# LEDmatrix2.net
KiCad netlist of a schematic drawn in Altium Designer
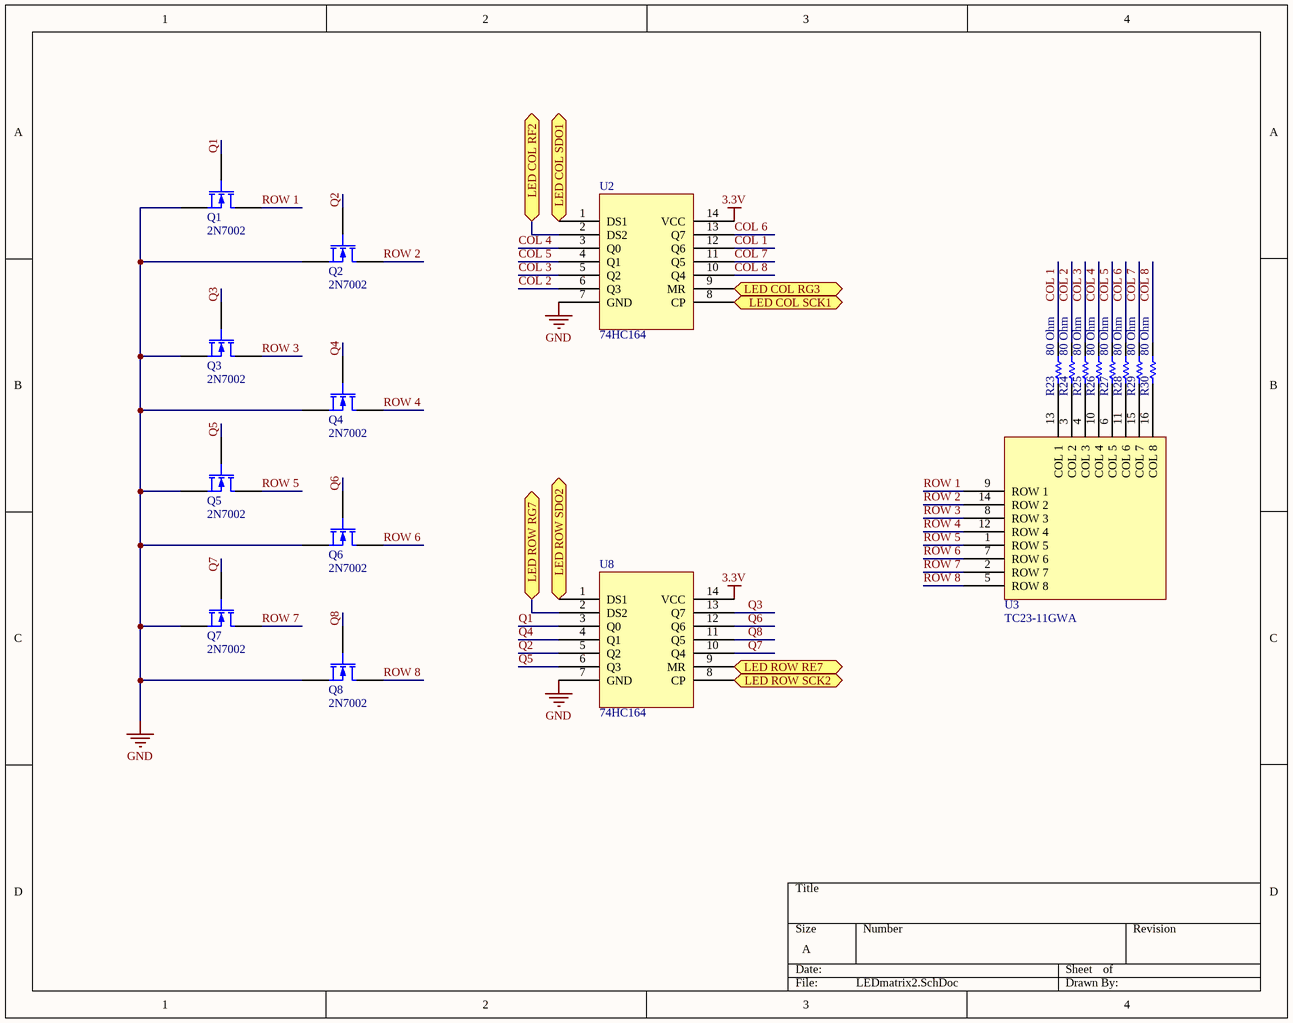
[diagram p0: LEDmatrix2.SchDoc]

(export (version "E")
  (design (tool "Eeschema 10.0.6"))
  (components
    (comp (ref "Q1")
      (value "2N7002")
      (footprint "Mosfet")
      (description "N-Channel MOSFET")
      (fields (field (name "PUBLISHER") "Altium Limited"))
      (libsource (lib "Miscellaneous Devices") (part "MOSFET-N"))
    )
    (comp (ref "Q2")
      (value "2N7002")
      (footprint "Mosfet")
      (description "N-Channel MOSFET")
      (fields (field (name "PUBLISHER") "Altium Limited"))
      (libsource (lib "Miscellaneous Devices") (part "MOSFET-N"))
    )
    (comp (ref "Q3")
      (value "2N7002")
      (footprint "Mosfet")
      (description "N-Channel MOSFET")
      (fields (field (name "PUBLISHER") "Altium Limited"))
      (libsource (lib "Miscellaneous Devices") (part "MOSFET-N"))
    )
    (comp (ref "Q4")
      (value "2N7002")
      (footprint "Mosfet")
      (description "N-Channel MOSFET")
      (fields (field (name "PUBLISHER") "Altium Limited"))
      (libsource (lib "Miscellaneous Devices") (part "MOSFET-N"))
    )
    (comp (ref "Q5")
      (value "2N7002")
      (footprint "Mosfet")
      (description "N-Channel MOSFET")
      (fields (field (name "PUBLISHER") "Altium Limited"))
      (libsource (lib "Miscellaneous Devices") (part "MOSFET-N"))
    )
    (comp (ref "Q6")
      (value "2N7002")
      (footprint "Mosfet")
      (description "N-Channel MOSFET")
      (fields (field (name "PUBLISHER") "Altium Limited"))
      (libsource (lib "Miscellaneous Devices") (part "MOSFET-N"))
    )
    (comp (ref "Q7")
      (value "2N7002")
      (footprint "Mosfet")
      (description "N-Channel MOSFET")
      (fields (field (name "PUBLISHER") "Altium Limited"))
      (libsource (lib "Miscellaneous Devices") (part "MOSFET-N"))
    )
    (comp (ref "Q8")
      (value "2N7002")
      (footprint "Mosfet")
      (description "N-Channel MOSFET")
      (fields (field (name "PUBLISHER") "Altium Limited"))
      (libsource (lib "Miscellaneous Devices") (part "MOSFET-N"))
    )
    (comp (ref "R23")
      (value "80 Ohm")
      (footprint "Resistor0603")
      (description "Resistor")
      (fields (field (name "PUBLISHER") "Altium Limited"))
      (libsource (lib "Miscellaneous Devices") (part "Res1"))
    )
    (comp (ref "R24")
      (value "80 Ohm")
      (footprint "Resistor0603")
      (description "Resistor")
      (fields (field (name "PUBLISHER") "Altium Limited"))
      (libsource (lib "Miscellaneous Devices") (part "Res1"))
    )
    (comp (ref "R25")
      (value "80 Ohm")
      (footprint "Resistor0603")
      (description "Resistor")
      (fields (field (name "PUBLISHER") "Altium Limited"))
      (libsource (lib "Miscellaneous Devices") (part "Res1"))
    )
    (comp (ref "R26")
      (value "80 Ohm")
      (footprint "Resistor0603")
      (description "Resistor")
      (fields (field (name "PUBLISHER") "Altium Limited"))
      (libsource (lib "Miscellaneous Devices") (part "Res1"))
    )
    (comp (ref "R27")
      (value "80 Ohm")
      (footprint "Resistor0603")
      (description "Resistor")
      (fields (field (name "PUBLISHER") "Altium Limited"))
      (libsource (lib "Miscellaneous Devices") (part "Res1"))
    )
    (comp (ref "R28")
      (value "80 Ohm")
      (footprint "Resistor0603")
      (description "Resistor")
      (fields (field (name "PUBLISHER") "Altium Limited"))
      (libsource (lib "Miscellaneous Devices") (part "Res1"))
    )
    (comp (ref "R29")
      (value "80 Ohm")
      (footprint "Resistor0603")
      (description "Resistor")
      (fields (field (name "PUBLISHER") "Altium Limited"))
      (libsource (lib "Miscellaneous Devices") (part "Res1"))
    )
    (comp (ref "R30")
      (value "80 Ohm")
      (footprint "Resistor0603")
      (description "Resistor")
      (fields (field (name "PUBLISHER") "Altium Limited"))
      (libsource (lib "Miscellaneous Devices") (part "Res1"))
    )
    (comp (ref "U2")
      (value "74HC164")
      (footprint "SHIFT REGISTER")
      (libsource (lib "PROBOT_Schema_Library") (part "Shift Register"))
    )
    (comp (ref "U3")
      (value "TC23-11GWA")
      (footprint "LEDPANEL")
      (libsource (lib "PROBOT_Schema_Library") (part "LED Dot Matrix"))
    )
    (comp (ref "U8")
      (value "74HC164")
      (footprint "SHIFT REGISTER")
      (libsource (lib "PROBOT_Schema_Library") (part "Shift Register"))
    )
  )
  (nets
    (net (code "1") (name "/COL 1") (class "Default")
      (node (ref "R23") (pin "2") (pinfunction "2_2") (pintype "passive"))
      (node (ref "U2") (pin "12") (pinfunction "Q6_12") (pintype "passive"))
    )
    (net (code "2") (name "/COL 2") (class "Default")
      (node (ref "R24") (pin "2") (pinfunction "2_2") (pintype "passive"))
      (node (ref "U2") (pin "6") (pinfunction "Q3_6") (pintype "passive"))
    )
    (net (code "3") (name "/COL 3") (class "Default")
      (node (ref "R25") (pin "2") (pinfunction "2_2") (pintype "passive"))
      (node (ref "U2") (pin "5") (pinfunction "Q2_5") (pintype "passive"))
    )
    (net (code "4") (name "/COL 4") (class "Default")
      (node (ref "R26") (pin "2") (pinfunction "2_2") (pintype "passive"))
      (node (ref "U2") (pin "3") (pinfunction "Q0_3") (pintype "passive"))
    )
    (net (code "5") (name "/COL 5") (class "Default")
      (node (ref "R27") (pin "2") (pinfunction "2_2") (pintype "passive"))
      (node (ref "U2") (pin "4") (pinfunction "Q1_4") (pintype "passive"))
    )
    (net (code "6") (name "/COL 6") (class "Default")
      (node (ref "R28") (pin "2") (pinfunction "2_2") (pintype "passive"))
      (node (ref "U2") (pin "13") (pinfunction "Q7_13") (pintype "passive"))
    )
    (net (code "7") (name "/COL 7") (class "Default")
      (node (ref "R29") (pin "2") (pinfunction "2_2") (pintype "passive"))
      (node (ref "U2") (pin "11") (pinfunction "Q5_11") (pintype "passive"))
    )
    (net (code "8") (name "/COL 8") (class "Default")
      (node (ref "R30") (pin "2") (pinfunction "2_2") (pintype "passive"))
      (node (ref "U2") (pin "10") (pinfunction "Q4_10") (pintype "passive"))
    )
    (net (code "9") (name "/LED COL RF2") (class "Default")
      (node (ref "U2") (pin "2") (pinfunction "DS2_2") (pintype "passive"))
    )
    (net (code "10") (name "/LED COL RG3") (class "Default")
      (node (ref "U2") (pin "9") (pinfunction "MR_9") (pintype "passive"))
    )
    (net (code "11") (name "/LED COL SCK1") (class "Default")
      (node (ref "U2") (pin "8") (pinfunction "CP_8") (pintype "passive"))
    )
    (net (code "12") (name "/LED COL SDO1") (class "Default")
      (node (ref "U2") (pin "1") (pinfunction "DS1_1") (pintype "passive"))
    )
    (net (code "13") (name "/LED ROW RE7") (class "Default")
      (node (ref "U8") (pin "9") (pinfunction "MR_9") (pintype "passive"))
    )
    (net (code "14") (name "/LED ROW RG7") (class "Default")
      (node (ref "U8") (pin "2") (pinfunction "DS2_2") (pintype "passive"))
    )
    (net (code "15") (name "/LED ROW SCK2") (class "Default")
      (node (ref "U8") (pin "8") (pinfunction "CP_8") (pintype "passive"))
    )
    (net (code "16") (name "/LED ROW SDO2") (class "Default")
      (node (ref "U8") (pin "1") (pinfunction "DS1_1") (pintype "passive"))
    )
    (net (code "17") (name "/Q1") (class "Default")
      (node (ref "Q1") (pin "2") (pinfunction "G_2") (pintype "passive"))
      (node (ref "U8") (pin "3") (pinfunction "Q0_3") (pintype "passive"))
    )
    (net (code "18") (name "/Q2") (class "Default")
      (node (ref "Q2") (pin "2") (pinfunction "G_2") (pintype "passive"))
      (node (ref "U8") (pin "5") (pinfunction "Q2_5") (pintype "passive"))
    )
    (net (code "19") (name "/Q3") (class "Default")
      (node (ref "Q3") (pin "2") (pinfunction "G_2") (pintype "passive"))
      (node (ref "U8") (pin "13") (pinfunction "Q7_13") (pintype "passive"))
    )
    (net (code "20") (name "/Q4") (class "Default")
      (node (ref "Q4") (pin "2") (pinfunction "G_2") (pintype "passive"))
      (node (ref "U8") (pin "4") (pinfunction "Q1_4") (pintype "passive"))
    )
    (net (code "21") (name "/Q5") (class "Default")
      (node (ref "Q5") (pin "2") (pinfunction "G_2") (pintype "passive"))
      (node (ref "U8") (pin "6") (pinfunction "Q3_6") (pintype "passive"))
    )
    (net (code "22") (name "/Q6") (class "Default")
      (node (ref "Q6") (pin "2") (pinfunction "G_2") (pintype "passive"))
      (node (ref "U8") (pin "12") (pinfunction "Q6_12") (pintype "passive"))
    )
    (net (code "23") (name "/Q7") (class "Default")
      (node (ref "Q7") (pin "2") (pinfunction "G_2") (pintype "passive"))
      (node (ref "U8") (pin "10") (pinfunction "Q4_10") (pintype "passive"))
    )
    (net (code "24") (name "/Q8") (class "Default")
      (node (ref "Q8") (pin "2") (pinfunction "G_2") (pintype "passive"))
      (node (ref "U8") (pin "11") (pinfunction "Q5_11") (pintype "passive"))
    )
    (net (code "25") (name "/ROW 1") (class "Default")
      (node (ref "Q1") (pin "1") (pinfunction "D_1") (pintype "passive"))
      (node (ref "U3") (pin "9") (pinfunction "ROW_1_9") (pintype "passive"))
    )
    (net (code "26") (name "/ROW 2") (class "Default")
      (node (ref "Q2") (pin "1") (pinfunction "D_1") (pintype "passive"))
      (node (ref "U3") (pin "14") (pinfunction "ROW_2_14") (pintype "passive"))
    )
    (net (code "27") (name "/ROW 3") (class "Default")
      (node (ref "Q3") (pin "1") (pinfunction "D_1") (pintype "passive"))
      (node (ref "U3") (pin "8") (pinfunction "ROW_3_8") (pintype "passive"))
    )
    (net (code "28") (name "/ROW 4") (class "Default")
      (node (ref "Q4") (pin "1") (pinfunction "D_1") (pintype "passive"))
      (node (ref "U3") (pin "12") (pinfunction "ROW_4_12") (pintype "passive"))
    )
    (net (code "29") (name "/ROW 5") (class "Default")
      (node (ref "Q5") (pin "1") (pinfunction "D_1") (pintype "passive"))
      (node (ref "U3") (pin "1") (pinfunction "ROW_5_1") (pintype "passive"))
    )
    (net (code "30") (name "/ROW 6") (class "Default")
      (node (ref "Q6") (pin "1") (pinfunction "D_1") (pintype "passive"))
      (node (ref "U3") (pin "7") (pinfunction "ROW_6_7") (pintype "passive"))
    )
    (net (code "31") (name "/ROW 7") (class "Default")
      (node (ref "Q7") (pin "1") (pinfunction "D_1") (pintype "passive"))
      (node (ref "U3") (pin "2") (pinfunction "ROW_7_2") (pintype "passive"))
    )
    (net (code "32") (name "/ROW 8") (class "Default")
      (node (ref "Q8") (pin "1") (pinfunction "D_1") (pintype "passive"))
      (node (ref "U3") (pin "5") (pinfunction "ROW_8_5") (pintype "passive"))
    )
    (net (code "33") (name "3.3V") (class "Default")
      (node (ref "U2") (pin "14") (pinfunction "VCC_14") (pintype "passive"))
      (node (ref "U8") (pin "14") (pinfunction "VCC_14") (pintype "passive"))
    )
    (net (code "34") (name "GND") (class "Default")
      (node (ref "Q1") (pin "3") (pinfunction "S_3") (pintype "passive"))
      (node (ref "Q2") (pin "3") (pinfunction "S_3") (pintype "passive"))
      (node (ref "Q3") (pin "3") (pinfunction "S_3") (pintype "passive"))
      (node (ref "Q4") (pin "3") (pinfunction "S_3") (pintype "passive"))
      (node (ref "Q5") (pin "3") (pinfunction "S_3") (pintype "passive"))
      (node (ref "Q6") (pin "3") (pinfunction "S_3") (pintype "passive"))
      (node (ref "Q7") (pin "3") (pinfunction "S_3") (pintype "passive"))
      (node (ref "Q8") (pin "3") (pinfunction "S_3") (pintype "passive"))
      (node (ref "U2") (pin "7") (pinfunction "GND_7") (pintype "passive"))
      (node (ref "U8") (pin "7") (pinfunction "GND_7") (pintype "passive"))
    )
    (net (code "35") (name "Net-(U3-COL_1)") (class "Default")
      (node (ref "R23") (pin "1") (pinfunction "1_1") (pintype "passive"))
      (node (ref "U3") (pin "13") (pinfunction "COL_1_13") (pintype "passive"))
    )
    (net (code "36") (name "Net-(U3-COL_2)") (class "Default")
      (node (ref "R24") (pin "1") (pinfunction "1_1") (pintype "passive"))
      (node (ref "U3") (pin "3") (pinfunction "COL_2_3") (pintype "passive"))
    )
    (net (code "37") (name "Net-(U3-COL_3)") (class "Default")
      (node (ref "R25") (pin "1") (pinfunction "1_1") (pintype "passive"))
      (node (ref "U3") (pin "4") (pinfunction "COL_3_4") (pintype "passive"))
    )
    (net (code "38") (name "Net-(U3-COL_4)") (class "Default")
      (node (ref "R26") (pin "1") (pinfunction "1_1") (pintype "passive"))
      (node (ref "U3") (pin "10") (pinfunction "COL_4_10") (pintype "passive"))
    )
    (net (code "39") (name "Net-(U3-COL_5)") (class "Default")
      (node (ref "R27") (pin "1") (pinfunction "1_1") (pintype "passive"))
      (node (ref "U3") (pin "6") (pinfunction "COL_5_6") (pintype "passive"))
    )
    (net (code "40") (name "Net-(U3-COL_6)") (class "Default")
      (node (ref "R28") (pin "1") (pinfunction "1_1") (pintype "passive"))
      (node (ref "U3") (pin "11") (pinfunction "COL_6_11") (pintype "passive"))
    )
    (net (code "41") (name "Net-(U3-COL_7)") (class "Default")
      (node (ref "R29") (pin "1") (pinfunction "1_1") (pintype "passive"))
      (node (ref "U3") (pin "15") (pinfunction "COL_7_15") (pintype "passive"))
    )
    (net (code "42") (name "Net-(U3-COL_8)") (class "Default")
      (node (ref "R30") (pin "1") (pinfunction "1_1") (pintype "passive"))
      (node (ref "U3") (pin "16") (pinfunction "COL_8_16") (pintype "passive"))
    )
  )
)
